# Sheet3.net
KiCad netlist of a schematic drawn in Altium Designer
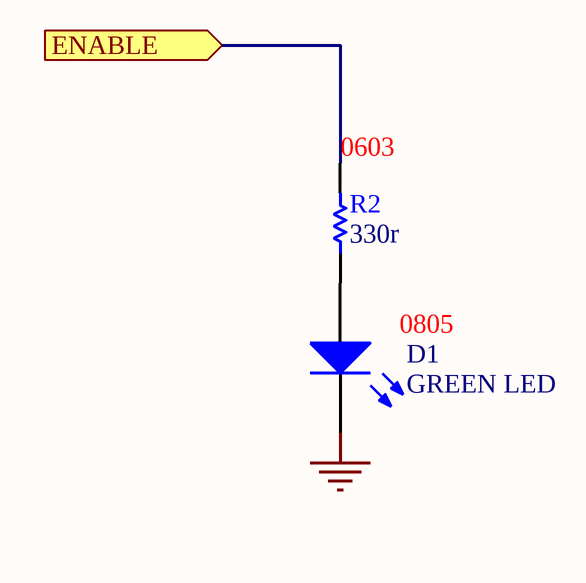
[diagram p0: Sheet3.SchDoc]

(export (version "E")
  (design (tool "Eeschema 10.0.6"))
  (components
    (comp (ref "D1")
      (value "GREEN LED")
      (footprint "3.2X1.6X1.1")
      (description "Typical RED, GREEN, YELLOW, AMBER GaAs LED")
      (fields (field (name "PUBLISHER") "Altium Limited"))
      (libsource (lib "Miscellaneous Devices") (part "LED2"))
    )
    (comp (ref "R2")
      (value "330r")
      (footprint "AXIAL-0.3")
      (description "Resistor")
      (fields (field (name "PUBLISHER") "Altium Limited"))
      (libsource (lib "Miscellaneous Devices") (part "Res1"))
    )
  )
  (nets
    (net (code "1") (name "/ENABLE") (class "Default")
      (node (ref "R2") (pin "2") (pinfunction "2_2") (pintype "passive"))
    )
    (net (code "2") (name "GND") (class "Default")
      (node (ref "D1") (pin "2") (pinfunction "K_2") (pintype "passive"))
    )
    (net (code "3") (name "Net-(D1-A)") (class "Default")
      (node (ref "D1") (pin "1") (pinfunction "A_1") (pintype "passive"))
      (node (ref "R2") (pin "1") (pinfunction "1_1") (pintype "passive"))
    )
  )
)
